# ttl-bob.net
KiCad netlist of a schematic drawn in EAGLE
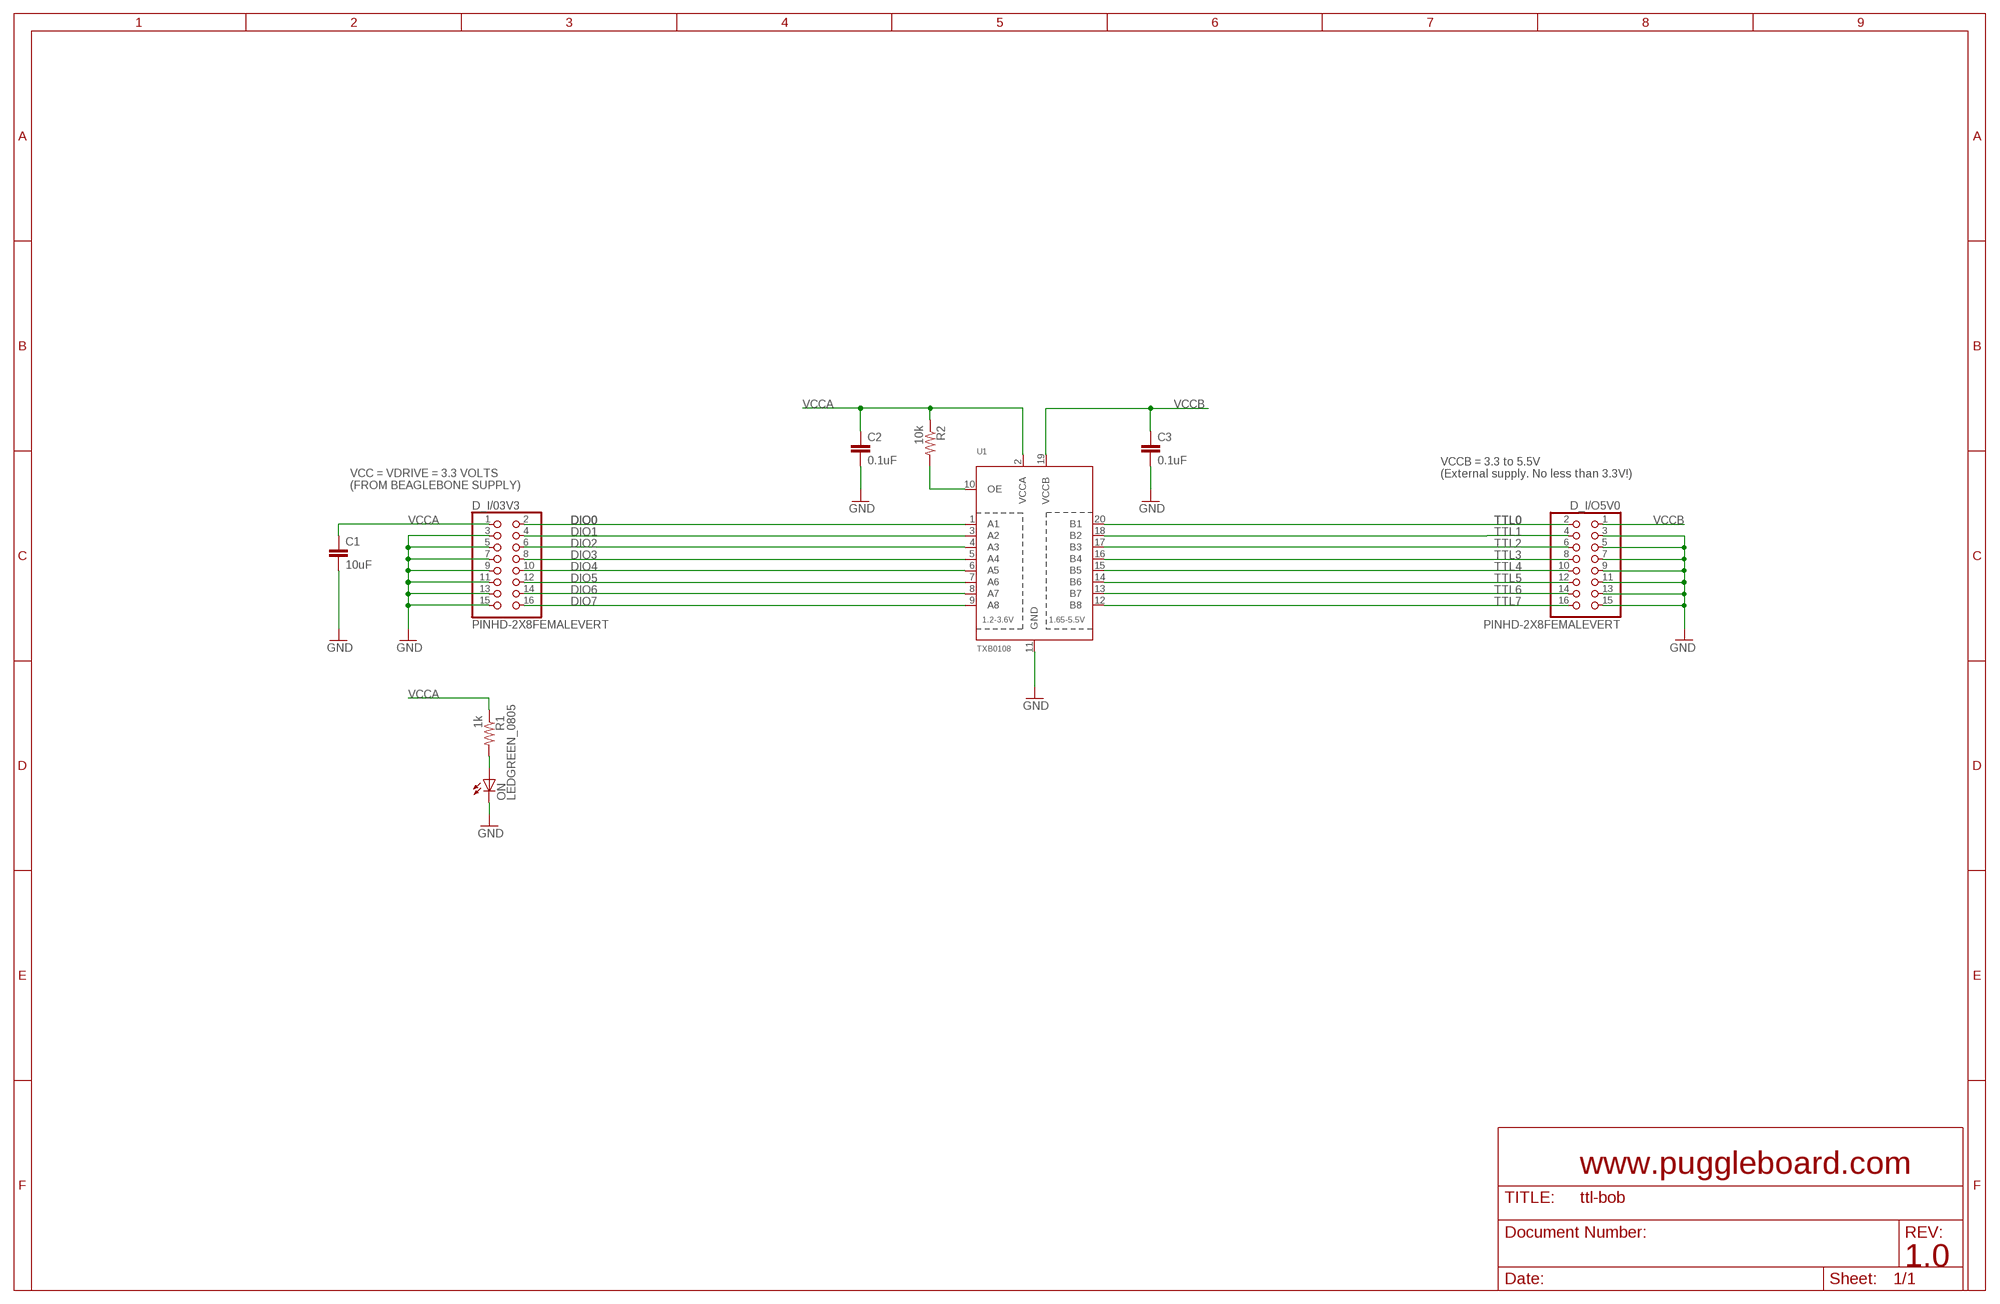
[diagram p0: schematic, sheet 1]

(export (version "E")
  (design (tool "Eeschema 10.0.6"))
  (components
    (comp (ref "C1")
      (value "10uF")
      (footprint "eagle-import:0805")
      (fields (field (name "PARTNO") "C2012X5R1Cxxxxxxx"))
      (libsource (lib "eagle-import") (part "C_0805"))
    )
    (comp (ref "C2")
      (value "0.1uF")
      (footprint "eagle-import:0603")
      (libsource (lib "eagle-import") (part "C_0603"))
    )
    (comp (ref "C3")
      (value "0.1uF")
      (footprint "eagle-import:0603")
      (libsource (lib "eagle-import") (part "C_0603"))
    )
    (comp (ref "D_I/03V3")
      (value "PINHD-2X8FEMALEVERT")
      (footprint "eagle-import:2X08")
      (fields (field (name "MPN") "PPPC082LFBN-RC"))
      (libsource (lib "eagle-import") (part "PINHD-2X8VERTFEMALE"))
    )
    (comp (ref "D_I/O5V0")
      (value "PINHD-2X8FEMALEVERT")
      (footprint "eagle-import:2X08")
      (fields (field (name "MPN") "PPPC082LFBN-RC"))
      (libsource (lib "eagle-import") (part "PINHD-2X8VERTFEMALE"))
    )
    (comp (ref "ON")
      (value "LEDGREEN_0805")
      (footprint "eagle-import:CHIP-LED0805")
      (fields (field (name "MPN") "Dialight"))
      (libsource (lib "eagle-import") (part "LED_0805GREEN"))
    )
    (comp (ref "R1")
      (value "1k")
      (footprint "eagle-import:0603")
      (fields
        (field (name "MPN") "ERJ-3EKFxxxxV")
        (field (name "DK") "P1.00KHCT-ND")
        (field (name "MPN_1") "ERJ-3EKF1001V")
      )
      (libsource (lib "eagle-import") (part "R_0603"))
    )
    (comp (ref "R2")
      (value "10k")
      (footprint "eagle-import:0603")
      (fields
        (field (name "MPN") "ERJ-3EKFxxxxV")
        (field (name "DK") "P10.0KHCT-ND")
        (field (name "MPN_1") "ERJ-3EKF1002V")
      )
      (libsource (lib "eagle-import") (part "R_0603"))
    )
    (comp (ref "U1")
      (value "TXB0108")
      (footprint "eagle-import:TSSOP20")
      (fields (field (name "MPN") "TXB0108PWR"))
      (libsource (lib "eagle-import") (part "TXB0108PWR"))
    )
  )
  (nets
    (net (code "1") (name "/DIO0") (class "Default")
      (node (ref "D_I/03V3") (pin "2") (pinfunction "2_2") (pintype "passive"))
      (node (ref "U1") (pin "1") (pinfunction "A1_1") (pintype "bidirectional"))
    )
    (net (code "2") (name "/DIO1") (class "Default")
      (node (ref "D_I/03V3") (pin "4") (pinfunction "4_4") (pintype "passive"))
      (node (ref "U1") (pin "3") (pinfunction "A2_3") (pintype "bidirectional"))
    )
    (net (code "3") (name "/DIO2") (class "Default")
      (node (ref "D_I/03V3") (pin "6") (pinfunction "6_6") (pintype "passive"))
      (node (ref "U1") (pin "4") (pinfunction "A3_4") (pintype "bidirectional"))
    )
    (net (code "4") (name "/DIO3") (class "Default")
      (node (ref "D_I/03V3") (pin "8") (pinfunction "8_8") (pintype "passive"))
      (node (ref "U1") (pin "5") (pinfunction "A4_5") (pintype "bidirectional"))
    )
    (net (code "5") (name "/DIO4") (class "Default")
      (node (ref "D_I/03V3") (pin "10") (pinfunction "10_10") (pintype "passive"))
      (node (ref "U1") (pin "6") (pinfunction "A5_6") (pintype "bidirectional"))
    )
    (net (code "6") (name "/DIO5") (class "Default")
      (node (ref "D_I/03V3") (pin "12") (pinfunction "12_12") (pintype "passive"))
      (node (ref "U1") (pin "7") (pinfunction "A6_7") (pintype "bidirectional"))
    )
    (net (code "7") (name "/DIO6") (class "Default")
      (node (ref "D_I/03V3") (pin "14") (pinfunction "14_14") (pintype "passive"))
      (node (ref "U1") (pin "8") (pinfunction "A7_8") (pintype "bidirectional"))
    )
    (net (code "8") (name "/DIO7") (class "Default")
      (node (ref "D_I/03V3") (pin "16") (pinfunction "16_16") (pintype "passive"))
      (node (ref "U1") (pin "9") (pinfunction "A8_9") (pintype "bidirectional"))
    )
    (net (code "9") (name "/TTL0") (class "Default")
      (node (ref "D_I/O5V0") (pin "2") (pinfunction "2_2") (pintype "passive"))
      (node (ref "U1") (pin "20") (pinfunction "B1_20") (pintype "bidirectional"))
    )
    (net (code "10") (name "/TTL1") (class "Default")
      (node (ref "D_I/O5V0") (pin "4") (pinfunction "4_4") (pintype "passive"))
      (node (ref "U1") (pin "18") (pinfunction "B2_18") (pintype "bidirectional"))
    )
    (net (code "11") (name "/TTL2") (class "Default")
      (node (ref "D_I/O5V0") (pin "6") (pinfunction "6_6") (pintype "passive"))
      (node (ref "U1") (pin "17") (pinfunction "B3_17") (pintype "bidirectional"))
    )
    (net (code "12") (name "/TTL3") (class "Default")
      (node (ref "D_I/O5V0") (pin "8") (pinfunction "8_8") (pintype "passive"))
      (node (ref "U1") (pin "16") (pinfunction "B4_16") (pintype "bidirectional"))
    )
    (net (code "13") (name "/TTL4") (class "Default")
      (node (ref "D_I/O5V0") (pin "10") (pinfunction "10_10") (pintype "passive"))
      (node (ref "U1") (pin "15") (pinfunction "B5_15") (pintype "bidirectional"))
    )
    (net (code "14") (name "/TTL5") (class "Default")
      (node (ref "D_I/O5V0") (pin "12") (pinfunction "12_12") (pintype "passive"))
      (node (ref "U1") (pin "14") (pinfunction "B6_14") (pintype "bidirectional"))
    )
    (net (code "15") (name "/TTL6") (class "Default")
      (node (ref "D_I/O5V0") (pin "14") (pinfunction "14_14") (pintype "passive"))
      (node (ref "U1") (pin "13") (pinfunction "B7_13") (pintype "bidirectional"))
    )
    (net (code "16") (name "/TTL7") (class "Default")
      (node (ref "D_I/O5V0") (pin "16") (pinfunction "16_16") (pintype "passive"))
      (node (ref "U1") (pin "12") (pinfunction "B8_12") (pintype "bidirectional"))
    )
    (net (code "17") (name "/VCCA") (class "Default")
      (node (ref "C1") (pin "1") (pinfunction "1_1") (pintype "passive"))
      (node (ref "C2") (pin "1") (pinfunction "1_1") (pintype "passive"))
      (node (ref "D_I/03V3") (pin "1") (pinfunction "1_1") (pintype "passive"))
      (node (ref "R1") (pin "1") (pinfunction "1_1") (pintype "passive"))
      (node (ref "R2") (pin "1") (pinfunction "1_1") (pintype "passive"))
      (node (ref "U1") (pin "2") (pinfunction "VCCA_2") (pintype "bidirectional"))
    )
    (net (code "18") (name "/VCCB") (class "Default")
      (node (ref "C3") (pin "1") (pinfunction "1_1") (pintype "passive"))
      (node (ref "D_I/O5V0") (pin "1") (pinfunction "1_1") (pintype "passive"))
      (node (ref "U1") (pin "19") (pinfunction "VCCB_19") (pintype "bidirectional"))
    )
    (net (code "19") (name "GND") (class "Default")
      (node (ref "C1") (pin "2") (pinfunction "2_2") (pintype "passive"))
      (node (ref "C2") (pin "2") (pinfunction "2_2") (pintype "passive"))
      (node (ref "C3") (pin "2") (pinfunction "2_2") (pintype "passive"))
      (node (ref "D_I/03V3") (pin "11") (pinfunction "11_11") (pintype "passive"))
      (node (ref "D_I/03V3") (pin "13") (pinfunction "13_13") (pintype "passive"))
      (node (ref "D_I/03V3") (pin "15") (pinfunction "15_15") (pintype "passive"))
      (node (ref "D_I/03V3") (pin "3") (pinfunction "3_3") (pintype "passive"))
      (node (ref "D_I/03V3") (pin "5") (pinfunction "5_5") (pintype "passive"))
      (node (ref "D_I/03V3") (pin "7") (pinfunction "7_7") (pintype "passive"))
      (node (ref "D_I/03V3") (pin "9") (pinfunction "9_9") (pintype "passive"))
      (node (ref "D_I/O5V0") (pin "11") (pinfunction "11_11") (pintype "passive"))
      (node (ref "D_I/O5V0") (pin "13") (pinfunction "13_13") (pintype "passive"))
      (node (ref "D_I/O5V0") (pin "15") (pinfunction "15_15") (pintype "passive"))
      (node (ref "D_I/O5V0") (pin "3") (pinfunction "3_3") (pintype "passive"))
      (node (ref "D_I/O5V0") (pin "5") (pinfunction "5_5") (pintype "passive"))
      (node (ref "D_I/O5V0") (pin "7") (pinfunction "7_7") (pintype "passive"))
      (node (ref "D_I/O5V0") (pin "9") (pinfunction "9_9") (pintype "passive"))
      (node (ref "ON") (pin "C") (pinfunction "C_C") (pintype "passive"))
      (node (ref "U1") (pin "11") (pinfunction "GND_11") (pintype "bidirectional"))
    )
    (net (code "20") (name "Net-(ON-PadA)") (class "Default")
      (node (ref "ON") (pin "A") (pinfunction "A_A") (pintype "passive"))
      (node (ref "R1") (pin "2") (pinfunction "2_2") (pintype "passive"))
    )
    (net (code "21") (name "Net-(U1-OE)") (class "Default")
      (node (ref "R2") (pin "2") (pinfunction "2_2") (pintype "passive"))
      (node (ref "U1") (pin "10") (pinfunction "OE_10") (pintype "bidirectional"))
    )
  )
)
